# SCH_PCBrelayLM2596_2021-11-15.net
KiCad netlist of a schematic drawn in EasyEDA
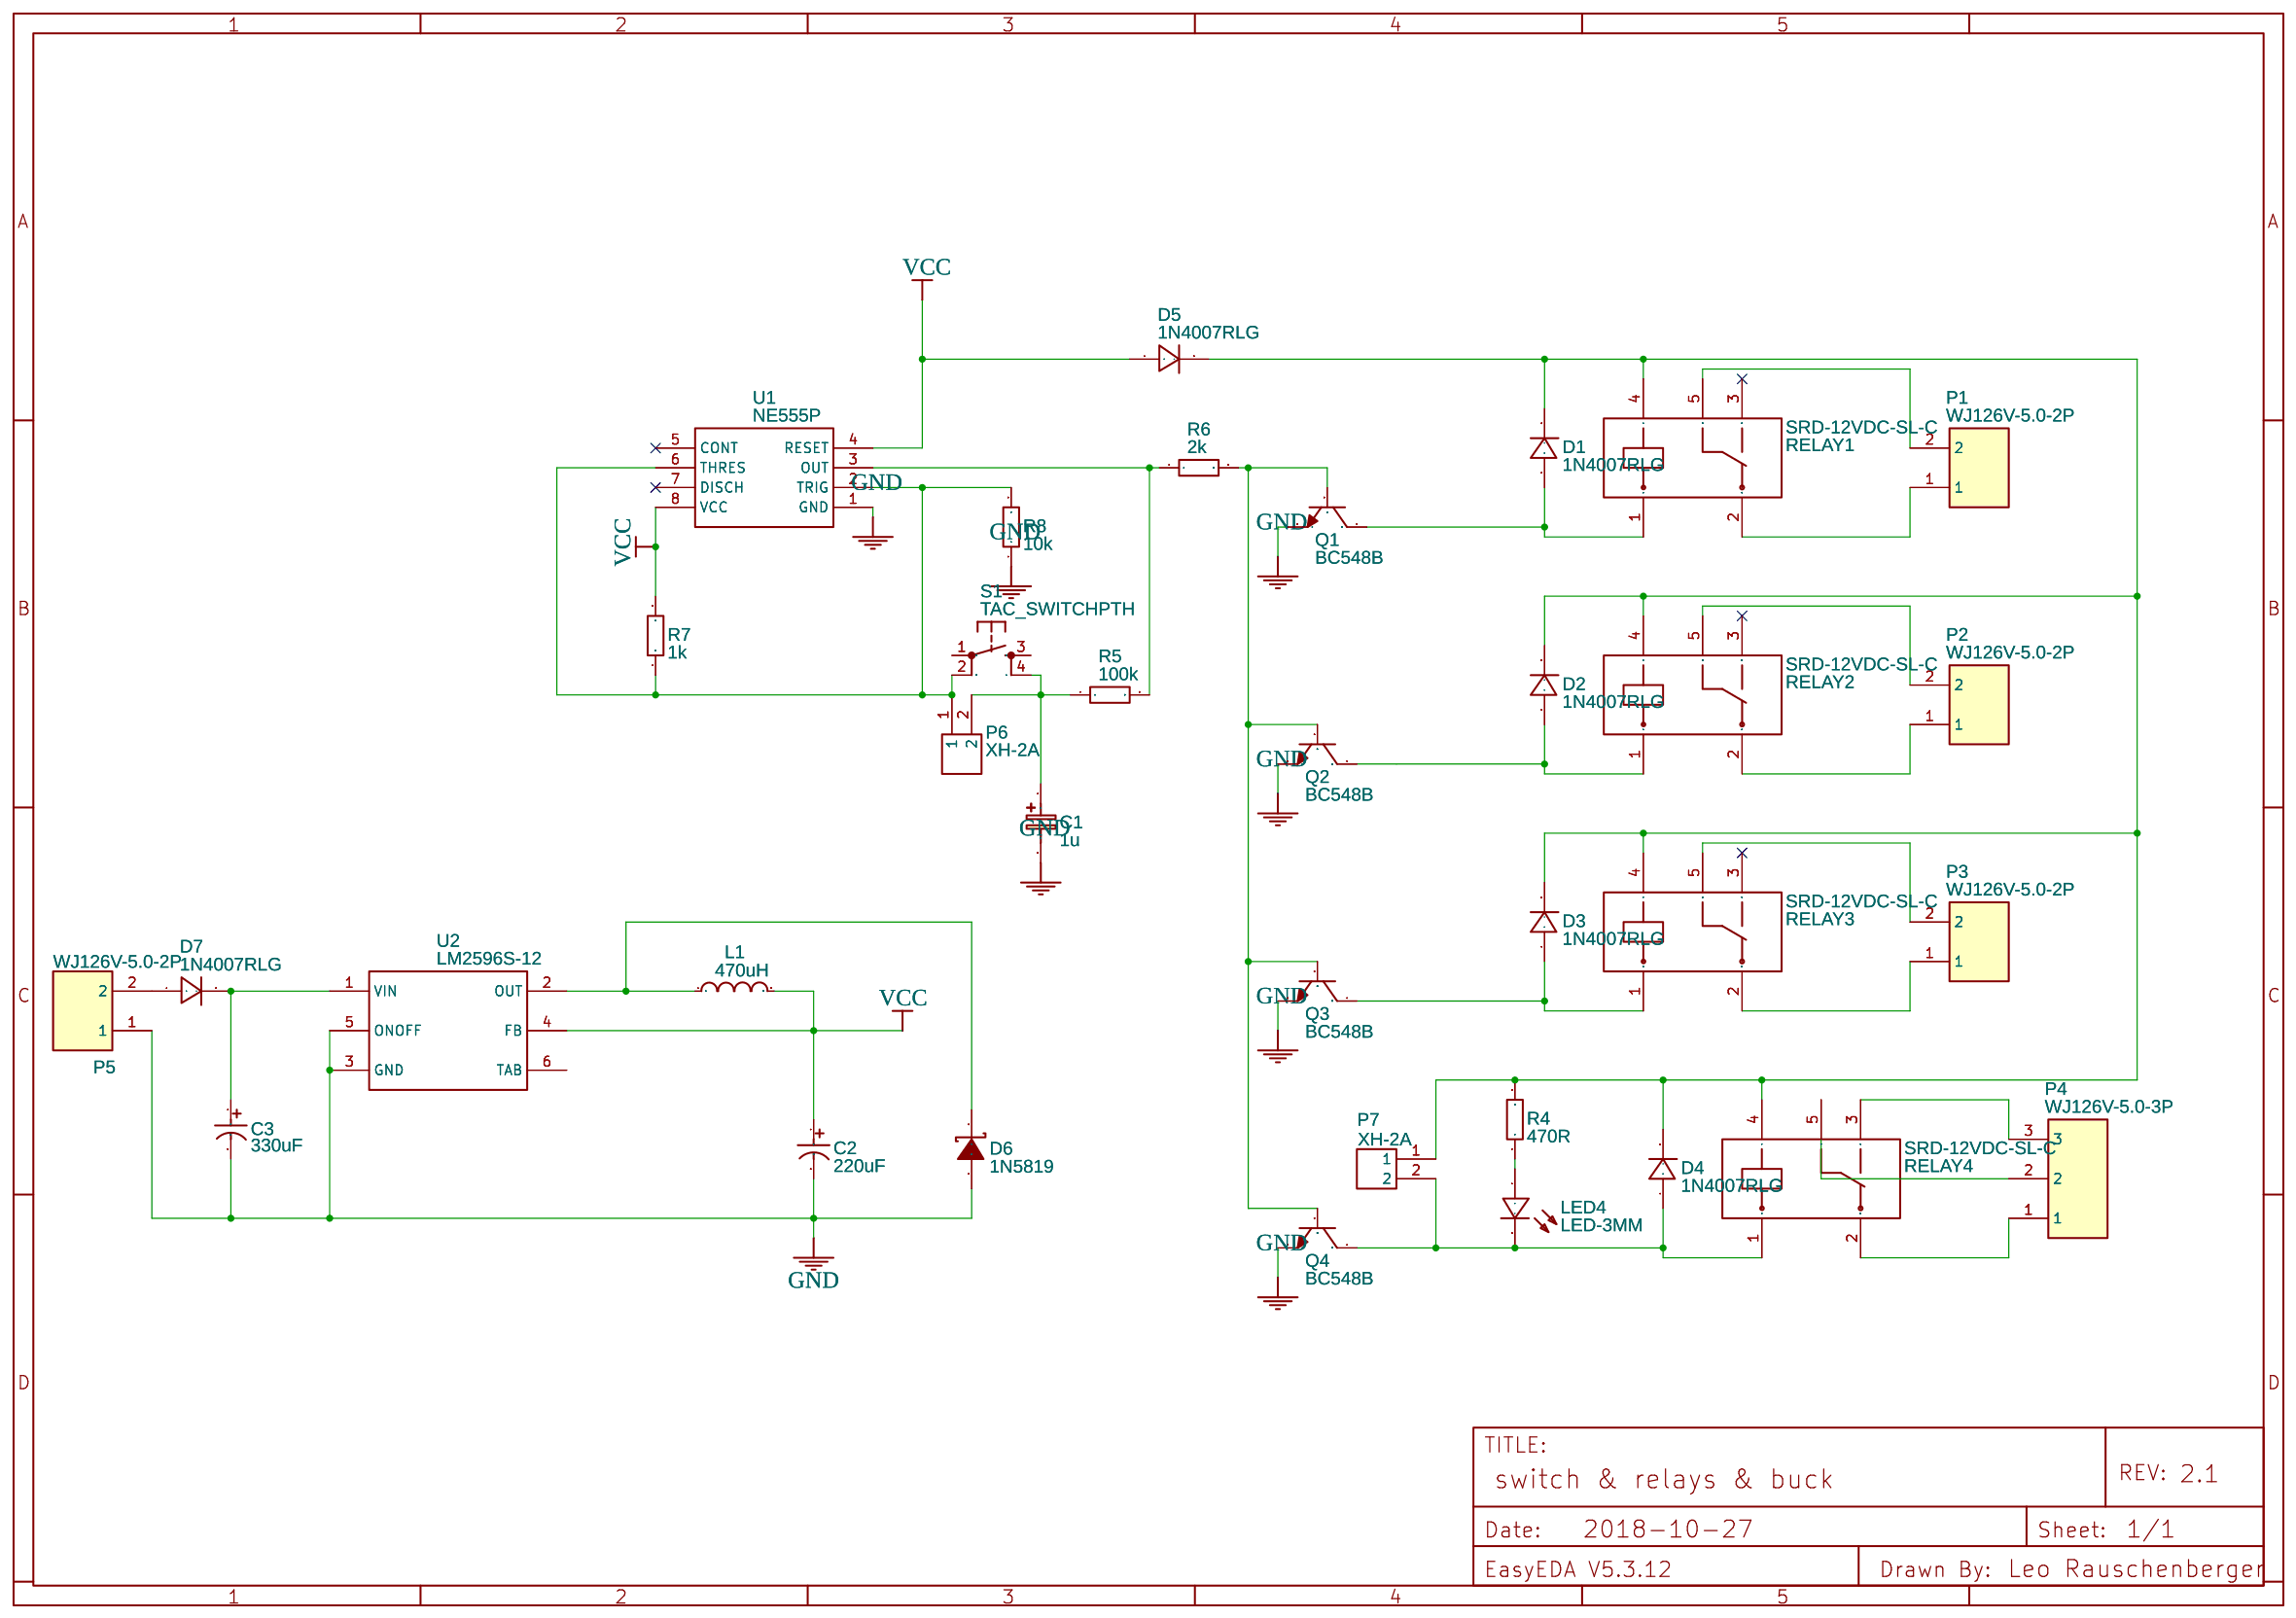
[diagram p0: schematic sheet]

(export (version "E")
  (design (tool "Eeschema 10.0.6"))
  (components
    (comp (ref "C1")
      (value "1u")
      (fields (field (name "BOM_Manufacturer Part") "?"))
      (libsource (lib "") (part "Capacitor"))
    )
    (comp (ref "C2")
      (value "220uF")
      (fields (field (name "BOM_Manufacturer Part") "220uF 25V") (field (name "BOM_Supplier Part") "C12450"))
      (libsource (lib "") (part "220uF 25V"))
    )
    (comp (ref "C3")
      (value "330uF")
      (fields
        (field (name "BOM_Manufacturer Part") "330uF 50V 10*20")
        (field (name "BOM_Supplier Part") "C45108")
      )
      (libsource (lib "") (part "330uF 50V 10*20"))
    )
    (comp (ref "D1")
      (value "1N4007RLG")
      (fields (field (name "BOM_Supplier Part") "C53568"))
      (libsource (lib "") (part "Unknown_775_220"))
    )
    (comp (ref "D2")
      (value "1N4007RLG")
      (fields (field (name "BOM_Supplier Part") "C53568"))
      (libsource (lib "") (part "Unknown_775_340"))
    )
    (comp (ref "D3")
      (value "1N4007RLG")
      (fields (field (name "BOM_Supplier Part") "C53568"))
      (libsource (lib "") (part "Unknown_775_460"))
    )
    (comp (ref "D4")
      (value "1N4007RLG")
      (fields (field (name "BOM_Supplier Part") "C53568"))
      (libsource (lib "") (part "Unknown_835_585"))
    )
    (comp (ref "D5")
      (value "1N4007RLG")
      (fields (field (name "BOM_Supplier Part") "C53568"))
      (libsource (lib "") (part "Unknown_585_175"))
    )
    (comp (ref "D6")
      (value "1N5819")
      (fields (field (name "BOM_Supplier Part") "C84618"))
      (libsource (lib "") (part "Unknown_485_575"))
    )
    (comp (ref "D7")
      (value "1N4007RLG")
      (fields (field (name "BOM_Supplier Part") "C53568"))
      (libsource (lib "") (part "Unknown_90_495"))
    )
    (comp (ref "L1")
      (value "470uH")
      (fields
        (field (name "BOM_Manufacturer Part") "VLU0608-471K")
        (field (name "BOM_Supplier Part") "C128033")
      )
      (libsource (lib "") (part "VLU0608-471K"))
    )
    (comp (ref "LED4")
      (value "LED-3MM")
      (fields
        (field (name "BOM_Manufacturer Part") "204-10UYC/S530-A3")
        (field (name "BOM_Supplier Part") "undefined")
      )
      (libsource (lib "") (part "Unknown_760_605"))
    )
    (comp (ref "P1")
      (value "WJ126V-5.0-2P")
      (fields (field (name "BOM_Supplier Part") "C8404"))
      (libsource (lib "") (part "Unknown_970_230"))
    )
    (comp (ref "P2")
      (value "WJ126V-5.0-2P")
      (fields (field (name "BOM_Supplier Part") "C8404"))
      (libsource (lib "") (part "Unknown_970_350"))
    )
    (comp (ref "P3")
      (value "WJ126V-5.0-2P")
      (fields (field (name "BOM_Supplier Part") "C8404"))
      (libsource (lib "") (part "Unknown_970_470"))
    )
    (comp (ref "P4")
      (value "WJ126V-5.0-3P")
      (fields (field (name "BOM_Supplier Part") "C8401"))
      (libsource (lib "") (part "Unknown_1020_590"))
    )
    (comp (ref "P5")
      (value "WJ126V-5.0-2P")
      (fields (field (name "BOM_Supplier Part") "C8404"))
      (libsource (lib "") (part "Unknown_60_505"))
    )
    (comp (ref "P6")
      (value "XH-2A")
      (fields (field (name "BOM_Supplier Part") "C20079"))
      (libsource (lib "") (part "Unknown_485_365"))
    )
    (comp (ref "P7")
      (value "XH-2A")
      (fields (field (name "BOM_Supplier Part") "C20079"))
      (libsource (lib "") (part "Unknown_700_590"))
    )
    (comp (ref "Q1")
      (value "BC548B")
      (fields (field (name "BOM_Supplier Part") "C36611"))
      (libsource (lib "") (part "Unknown_665_260"))
    )
    (comp (ref "Q2")
      (value "BC548B")
      (fields (field (name "BOM_Supplier Part") "C36611"))
      (libsource (lib "") (part "Unknown_660_380"))
    )
    (comp (ref "Q3")
      (value "BC548B")
      (fields (field (name "BOM_Supplier Part") "C36611"))
      (libsource (lib "") (part "Unknown_660_500"))
    )
    (comp (ref "Q4")
      (value "BC548B")
      (fields (field (name "BOM_Supplier Part") "C36611"))
      (libsource (lib "") (part "Unknown_660_625"))
    )
    (comp (ref "R4")
      (value "470R")
      (fields (field (name "BOM_Manufacturer Part") "?"))
      (libsource (lib "") (part "Resistor_1"))
    )
    (comp (ref "R5")
      (value "100k")
      (fields (field (name "BOM_Manufacturer Part") "?"))
      (libsource (lib "") (part "Resistor"))
    )
    (comp (ref "R6")
      (value "2k")
      (fields (field (name "BOM_Manufacturer Part") "?"))
      (libsource (lib "") (part "Resistor"))
    )
    (comp (ref "R7")
      (value "1k")
      (fields (field (name "BOM_Manufacturer Part") "?"))
      (libsource (lib "") (part "Resistor_1"))
    )
    (comp (ref "R8")
      (value "10k")
      (fields (field (name "BOM_Manufacturer Part") "?"))
      (libsource (lib "") (part "Resistor_1"))
    )
    (comp (ref "RELAY1")
      (value "SRD-12VDC-SL-C")
      (fields (field (name "BOM_Supplier Part") "C30431"))
      (libsource (lib "") (part "Unknown_855_225"))
    )
    (comp (ref "RELAY2")
      (value "SRD-12VDC-SL-C")
      (fields (field (name "BOM_Supplier Part") "C30431"))
      (libsource (lib "") (part "Unknown_855_345"))
    )
    (comp (ref "RELAY3")
      (value "SRD-12VDC-SL-C")
      (fields (field (name "BOM_Supplier Part") "C30431"))
      (libsource (lib "") (part "Unknown_855_465"))
    )
    (comp (ref "RELAY4")
      (value "SRD-12VDC-SL-C")
      (fields (field (name "BOM_Supplier Part") "C30431"))
      (libsource (lib "") (part "Unknown_915_590"))
    )
    (comp (ref "S1")
      (value "TAC_SWITCHPTH")
      (fields (field (name "BOM_Manufacturer Part") "?"))
      (libsource (lib "") (part "Unknown_495_325"))
    )
    (comp (ref "U1")
      (value "NE555P")
      (fields (field (name "BOM_Supplier Part") "C46749"))
      (libsource (lib "") (part "Unknown_385_240"))
    )
    (comp (ref "U2")
      (value "LM2596S-12")
      (fields
        (field (name "BOM_Manufacturer Part") "LM2596SX-12")
        (field (name "BOM_Supplier Part") "C17127")
      )
      (libsource (lib "") (part "Unknown_220_515"))
    )
  )
  (nets
    (net (code "1") (name "GND") (class "Default")
      (node (ref "C1") (pin "2") (pinfunction "2_2") (pintype "unspecified"))
      (node (ref "C2") (pin "2") (pinfunction "2_2") (pintype "input"))
      (node (ref "C3") (pin "2") (pinfunction "2_2") (pintype "input"))
      (node (ref "D6") (pin "1") (pinfunction "A_1") (pintype "unspecified"))
      (node (ref "P5") (pin "1") (pinfunction "1_1") (pintype "input"))
      (node (ref "Q1") (pin "3") (pinfunction "E_3") (pintype "unspecified"))
      (node (ref "Q2") (pin "3") (pinfunction "E_3") (pintype "unspecified"))
      (node (ref "Q3") (pin "3") (pinfunction "E_3") (pintype "unspecified"))
      (node (ref "Q4") (pin "3") (pinfunction "E_3") (pintype "unspecified"))
      (node (ref "R8") (pin "1") (pinfunction "1_1") (pintype "unspecified"))
      (node (ref "U1") (pin "1") (pinfunction "GND_1") (pintype "unspecified"))
      (node (ref "U2") (pin "3") (pinfunction "GND_3") (pintype "passive"))
      (node (ref "U2") (pin "5") (pinfunction "ONOFF_5") (pintype "unspecified"))
    )
    (net (code "2") (name "Net-(C1-Pad1)") (class "Default")
      (node (ref "C1") (pin "1") (pinfunction "1_1") (pintype "unspecified"))
      (node (ref "P6") (pin "2") (pinfunction "2_2") (pintype "unspecified"))
      (node (ref "R5") (pin "1") (pinfunction "1_1") (pintype "unspecified"))
      (node (ref "S1") (pin "4") (pinfunction "4_4") (pintype "unspecified"))
    )
    (net (code "3") (name "Net-(D1-+)") (class "Default")
      (node (ref "D1") (pin "1") (pinfunction "+_1") (pintype "unspecified"))
      (node (ref "Q1") (pin "1") (pinfunction "C_1") (pintype "unspecified"))
      (node (ref "RELAY1") (pin "1") (pinfunction "1_1") (pintype "input"))
    )
    (net (code "4") (name "Net-(D1--)") (class "Default")
      (node (ref "D1") (pin "2") (pinfunction "-_2") (pintype "unspecified"))
      (node (ref "D2") (pin "2") (pinfunction "-_2") (pintype "unspecified"))
      (node (ref "D3") (pin "2") (pinfunction "-_2") (pintype "unspecified"))
      (node (ref "D4") (pin "2") (pinfunction "-_2") (pintype "unspecified"))
      (node (ref "D5") (pin "2") (pinfunction "-_2") (pintype "unspecified"))
      (node (ref "P7") (pin "1") (pinfunction "1_1") (pintype "unspecified"))
      (node (ref "R4") (pin "2") (pinfunction "2_2") (pintype "unspecified"))
      (node (ref "RELAY1") (pin "4") (pinfunction "4_4") (pintype "input"))
      (node (ref "RELAY2") (pin "4") (pinfunction "4_4") (pintype "input"))
      (node (ref "RELAY3") (pin "4") (pinfunction "4_4") (pintype "input"))
      (node (ref "RELAY4") (pin "4") (pinfunction "4_4") (pintype "input"))
    )
    (net (code "5") (name "Net-(D2-+)") (class "Default")
      (node (ref "D2") (pin "1") (pinfunction "+_1") (pintype "unspecified"))
      (node (ref "Q2") (pin "1") (pinfunction "C_1") (pintype "unspecified"))
      (node (ref "RELAY2") (pin "1") (pinfunction "1_1") (pintype "input"))
    )
    (net (code "6") (name "Net-(D3-+)") (class "Default")
      (node (ref "D3") (pin "1") (pinfunction "+_1") (pintype "unspecified"))
      (node (ref "Q3") (pin "1") (pinfunction "C_1") (pintype "unspecified"))
      (node (ref "RELAY3") (pin "1") (pinfunction "1_1") (pintype "input"))
    )
    (net (code "7") (name "Net-(D4-+)") (class "Default")
      (node (ref "D4") (pin "1") (pinfunction "+_1") (pintype "unspecified"))
      (node (ref "LED4") (pin "2") (pinfunction "-_2") (pintype "unspecified"))
      (node (ref "P7") (pin "2") (pinfunction "2_2") (pintype "unspecified"))
      (node (ref "Q4") (pin "1") (pinfunction "C_1") (pintype "unspecified"))
      (node (ref "RELAY4") (pin "1") (pinfunction "1_1") (pintype "input"))
    )
    (net (code "8") (name "Net-(D6-K)") (class "Default")
      (node (ref "D6") (pin "2") (pinfunction "K_2") (pintype "unspecified"))
      (node (ref "L1") (pin "1") (pinfunction "1_1") (pintype "unspecified"))
      (node (ref "U2") (pin "2") (pinfunction "OUT_2") (pintype "passive"))
    )
    (net (code "9") (name "Net-(D7-+)") (class "Default")
      (node (ref "D7") (pin "1") (pinfunction "+_1") (pintype "unspecified"))
      (node (ref "P5") (pin "2") (pinfunction "2_2") (pintype "input"))
    )
    (net (code "10") (name "Net-(D7--)") (class "Default")
      (node (ref "C3") (pin "1") (pinfunction "1_1") (pintype "input"))
      (node (ref "D7") (pin "2") (pinfunction "-_2") (pintype "unspecified"))
      (node (ref "U2") (pin "1") (pinfunction "VIN_1") (pintype "passive"))
    )
    (net (code "11") (name "Net-(LED4-+)") (class "Default")
      (node (ref "LED4") (pin "1") (pinfunction "+_1") (pintype "unspecified"))
      (node (ref "R4") (pin "1") (pinfunction "1_1") (pintype "unspecified"))
    )
    (net (code "12") (name "Net-(P1-Pad1)") (class "Default")
      (node (ref "P1") (pin "1") (pinfunction "1_1") (pintype "input"))
      (node (ref "RELAY1") (pin "2") (pinfunction "2_2") (pintype "input"))
    )
    (net (code "13") (name "Net-(P1-Pad2)") (class "Default")
      (node (ref "P1") (pin "2") (pinfunction "2_2") (pintype "input"))
      (node (ref "RELAY1") (pin "5") (pinfunction "5_5") (pintype "input"))
    )
    (net (code "14") (name "Net-(P2-Pad1)") (class "Default")
      (node (ref "P2") (pin "1") (pinfunction "1_1") (pintype "input"))
      (node (ref "RELAY2") (pin "2") (pinfunction "2_2") (pintype "input"))
    )
    (net (code "15") (name "Net-(P2-Pad2)") (class "Default")
      (node (ref "P2") (pin "2") (pinfunction "2_2") (pintype "input"))
      (node (ref "RELAY2") (pin "5") (pinfunction "5_5") (pintype "input"))
    )
    (net (code "16") (name "Net-(P3-Pad1)") (class "Default")
      (node (ref "P3") (pin "1") (pinfunction "1_1") (pintype "input"))
      (node (ref "RELAY3") (pin "2") (pinfunction "2_2") (pintype "input"))
    )
    (net (code "17") (name "Net-(P3-Pad2)") (class "Default")
      (node (ref "P3") (pin "2") (pinfunction "2_2") (pintype "input"))
      (node (ref "RELAY3") (pin "5") (pinfunction "5_5") (pintype "input"))
    )
    (net (code "18") (name "Net-(P4-Pad1)") (class "Default")
      (node (ref "P4") (pin "1") (pinfunction "1_1") (pintype "input"))
      (node (ref "RELAY4") (pin "2") (pinfunction "2_2") (pintype "input"))
    )
    (net (code "19") (name "Net-(P4-Pad2)") (class "Default")
      (node (ref "P4") (pin "2") (pinfunction "2_2") (pintype "input"))
      (node (ref "RELAY4") (pin "5") (pinfunction "5_5") (pintype "input"))
    )
    (net (code "20") (name "Net-(P4-Pad3)") (class "Default")
      (node (ref "P4") (pin "3") (pinfunction "3_3") (pintype "input"))
      (node (ref "RELAY4") (pin "3") (pinfunction "3_3") (pintype "input"))
    )
    (net (code "21") (name "Net-(Q1-B)") (class "Default")
      (node (ref "Q1") (pin "2") (pinfunction "B_2") (pintype "unspecified"))
      (node (ref "Q2") (pin "2") (pinfunction "B_2") (pintype "unspecified"))
      (node (ref "Q3") (pin "2") (pinfunction "B_2") (pintype "unspecified"))
      (node (ref "Q4") (pin "2") (pinfunction "B_2") (pintype "unspecified"))
      (node (ref "R6") (pin "2") (pinfunction "2_2") (pintype "unspecified"))
    )
    (net (code "22") (name "Net-(U1-OUT)") (class "Default")
      (node (ref "R5") (pin "2") (pinfunction "2_2") (pintype "unspecified"))
      (node (ref "R6") (pin "1") (pinfunction "1_1") (pintype "unspecified"))
      (node (ref "U1") (pin "3") (pinfunction "OUT_3") (pintype "unspecified"))
    )
    (net (code "23") (name "Net-(U1-THRES)") (class "Default")
      (node (ref "P6") (pin "1") (pinfunction "1_1") (pintype "unspecified"))
      (node (ref "R7") (pin "1") (pinfunction "1_1") (pintype "unspecified"))
      (node (ref "R8") (pin "2") (pinfunction "2_2") (pintype "unspecified"))
      (node (ref "S1") (pin "2") (pinfunction "2_2") (pintype "unspecified"))
      (node (ref "U1") (pin "2") (pinfunction "TRIG_2") (pintype "unspecified"))
      (node (ref "U1") (pin "6") (pinfunction "THRES_6") (pintype "unspecified"))
    )
    (net (code "24") (name "VCC") (class "Default")
      (node (ref "C2") (pin "1") (pinfunction "1_1") (pintype "input"))
      (node (ref "D5") (pin "1") (pinfunction "+_1") (pintype "unspecified"))
      (node (ref "L1") (pin "2") (pinfunction "2_2") (pintype "unspecified"))
      (node (ref "R7") (pin "2") (pinfunction "2_2") (pintype "unspecified"))
      (node (ref "U1") (pin "4") (pinfunction "RESET_4") (pintype "unspecified"))
      (node (ref "U1") (pin "8") (pinfunction "VCC_8") (pintype "unspecified"))
      (node (ref "U2") (pin "4") (pinfunction "FB_4") (pintype "unspecified"))
    )
    (net (code "25") (name "unconnected-(RELAY1-Pad3)") (class "Default")
      (node (ref "RELAY1") (pin "3") (pinfunction "3_3") (pintype "input+no_connect"))
    )
    (net (code "26") (name "unconnected-(RELAY2-Pad3)") (class "Default")
      (node (ref "RELAY2") (pin "3") (pinfunction "3_3") (pintype "input+no_connect"))
    )
    (net (code "27") (name "unconnected-(RELAY3-Pad3)") (class "Default")
      (node (ref "RELAY3") (pin "3") (pinfunction "3_3") (pintype "input+no_connect"))
    )
    (net (code "28") (name "unconnected-(S1-Pad1)") (class "Default")
      (node (ref "S1") (pin "1") (pinfunction "1_1") (pintype "unspecified"))
    )
    (net (code "29") (name "unconnected-(S1-Pad3)") (class "Default")
      (node (ref "S1") (pin "3") (pinfunction "3_3") (pintype "unspecified"))
    )
    (net (code "30") (name "unconnected-(U1-CONT-Pad5)") (class "Default")
      (node (ref "U1") (pin "5") (pinfunction "CONT_5") (pintype "unspecified+no_connect"))
    )
    (net (code "31") (name "unconnected-(U1-DISCH-Pad7)") (class "Default")
      (node (ref "U1") (pin "7") (pinfunction "DISCH_7") (pintype "unspecified+no_connect"))
    )
    (net (code "32") (name "unconnected-(U2-TAB-Pad6)") (class "Default")
      (node (ref "U2") (pin "6") (pinfunction "TAB_6") (pintype "passive"))
    )
  )
)
